# Power_Distribution_-_Spares_6-9.net
KiCad netlist of a schematic drawn in Altium Designer
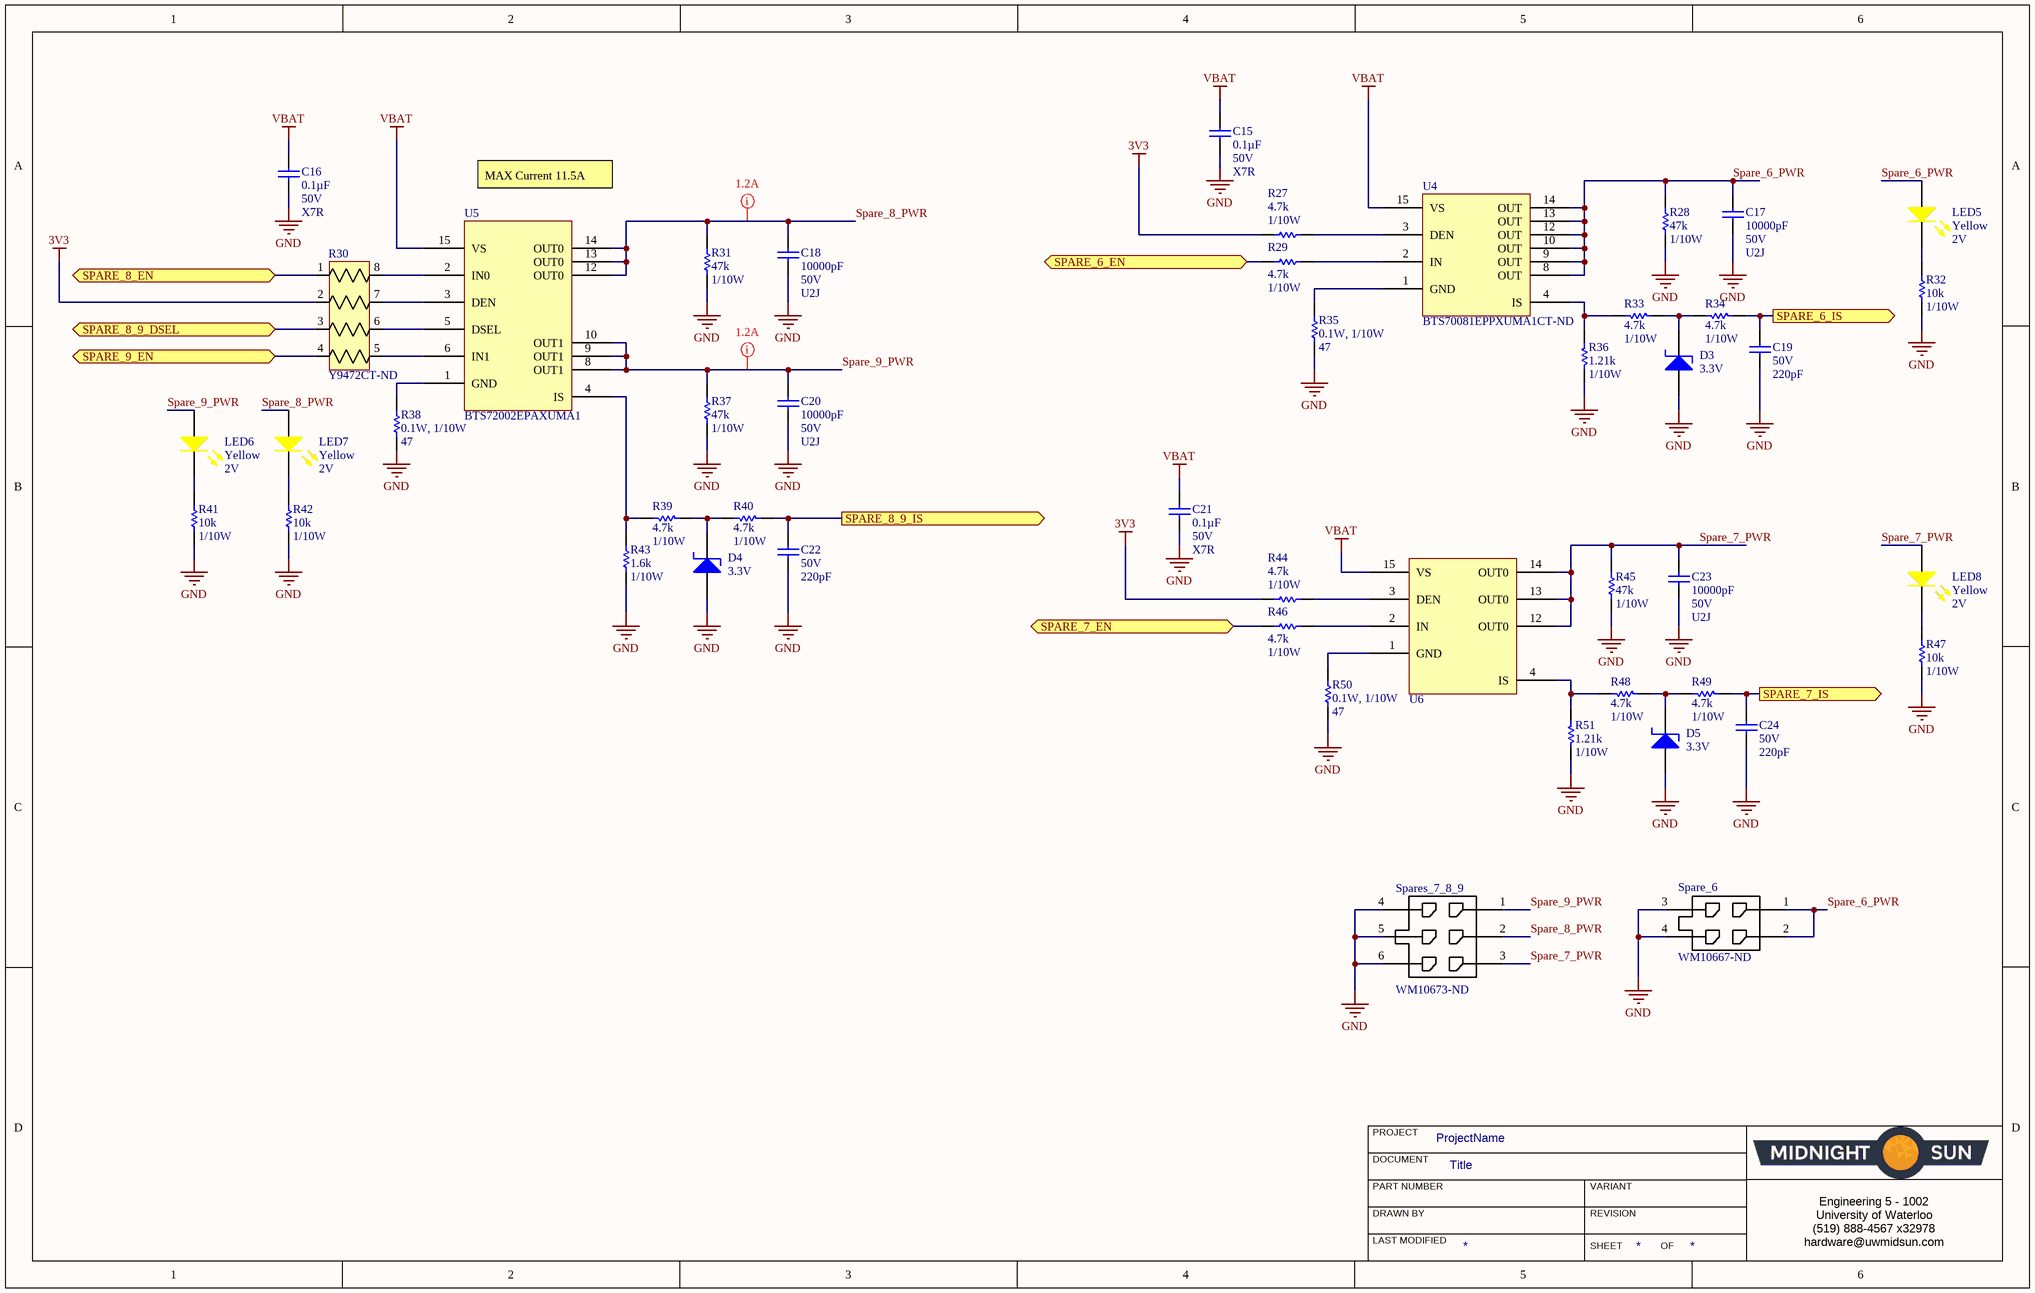
[diagram p0: Power Distribution - Spares 6-9.SchDoc]

(export (version "E")
  (design (tool "Eeschema 10.0.6"))
  (components
    (comp (ref "C15")
      (value "CAP CER 0.1UF 50V 10% X7R 0603")
      (footprint "CAP, 0603")
      (description "0.10µF ±10% 50V Ceramic Capacitor X7R 0603 (1608 Metric)")
      (fields
        (field (name "TOLERANCE") "±10%")
        (field (name "CAPACITANCE") "0.1µF")
        (field (name "VOLTAGE") "50V")
        (field (name "TEMPERATURE COEFFICIENT") "X7R")
      )
      (libsource (lib "Schematic Diagrams") (part "CAP CER 0.1UF 50V 10% X7R 0603"))
    )
    (comp (ref "C16")
      (value "CAP CER 0.1UF 50V 10% X7R 0603")
      (footprint "CAP, 0603")
      (description "0.10µF ±10% 50V Ceramic Capacitor X7R 0603 (1608 Metric)")
      (fields
        (field (name "TOLERANCE") "±10%")
        (field (name "CAPACITANCE") "0.1µF")
        (field (name "VOLTAGE") "50V")
        (field (name "TEMPERATURE COEFFICIENT") "X7R")
      )
      (libsource (lib "Schematic Diagrams") (part "CAP CER 0.1UF 50V 10% X7R 0603"))
    )
    (comp (ref "C17")
      (value "CAP CER 10nF 50V 5% X7R 0603")
      (footprint "CAP, 0603")
      (description "10000pF ±5% 50V Ceramic Capacitor U2J 0603 (1608 Metric)")
      (fields
        (field (name "TOLERANCE") "±5%")
        (field (name "CAPACITANCE") "10000pF")
        (field (name "VOLTAGE") "50V")
        (field (name "TEMPERATURE COEFFICIENT") "U2J")
      )
      (libsource (lib "Schematic Diagrams") (part "CAP CER 10nF 50V 5% X7R 0603"))
    )
    (comp (ref "C18")
      (value "CAP CER 10nF 50V 5% X7R 0603")
      (footprint "CAP, 0603")
      (description "10000pF ±5% 50V Ceramic Capacitor U2J 0603 (1608 Metric)")
      (fields
        (field (name "TOLERANCE") "±5%")
        (field (name "CAPACITANCE") "10000pF")
        (field (name "VOLTAGE") "50V")
        (field (name "TEMPERATURE COEFFICIENT") "U2J")
      )
      (libsource (lib "Schematic Diagrams") (part "CAP CER 10nF 50V 5% X7R 0603"))
    )
    (comp (ref "C19")
      (value "CAP CER 220PF 50V C0G/NP0 0603")
      (footprint "CAP, 0603")
      (description "220pF ±5% 50V Ceramic Capacitor C0G, NP0 0603 (1608 Metric)")
      (fields
        (field (name "MANUFACTURER") "KEMET")
        (field (name "TOLERANCE") "5%")
        (field (name "VOLTAGE RATING") "50V")
        (field (name "CAPACITANCE") "220pF")
      )
      (libsource (lib "Schematic Diagrams") (part "CAP CER 220PF 50V C0G/NP0 0603"))
    )
    (comp (ref "C20")
      (value "CAP CER 10nF 50V 5% X7R 0603")
      (footprint "CAP, 0603")
      (description "10000pF ±5% 50V Ceramic Capacitor U2J 0603 (1608 Metric)")
      (fields
        (field (name "TOLERANCE") "±5%")
        (field (name "CAPACITANCE") "10000pF")
        (field (name "VOLTAGE") "50V")
        (field (name "TEMPERATURE COEFFICIENT") "U2J")
      )
      (libsource (lib "Schematic Diagrams") (part "CAP CER 10nF 50V 5% X7R 0603"))
    )
    (comp (ref "C21")
      (value "CAP CER 0.1UF 50V 10% X7R 0603")
      (footprint "CAP, 0603")
      (description "0.10µF ±10% 50V Ceramic Capacitor X7R 0603 (1608 Metric)")
      (fields
        (field (name "TOLERANCE") "±10%")
        (field (name "CAPACITANCE") "0.1µF")
        (field (name "VOLTAGE") "50V")
        (field (name "TEMPERATURE COEFFICIENT") "X7R")
      )
      (libsource (lib "Schematic Diagrams") (part "CAP CER 0.1UF 50V 10% X7R 0603"))
    )
    (comp (ref "C22")
      (value "CAP CER 220PF 50V C0G/NP0 0603")
      (footprint "CAP, 0603")
      (description "220pF ±5% 50V Ceramic Capacitor C0G, NP0 0603 (1608 Metric)")
      (fields
        (field (name "MANUFACTURER") "KEMET")
        (field (name "TOLERANCE") "5%")
        (field (name "VOLTAGE RATING") "50V")
        (field (name "CAPACITANCE") "220pF")
      )
      (libsource (lib "Schematic Diagrams") (part "CAP CER 220PF 50V C0G/NP0 0603"))
    )
    (comp (ref "C23")
      (value "CAP CER 10nF 50V 5% X7R 0603")
      (footprint "CAP, 0603")
      (description "10000pF ±5% 50V Ceramic Capacitor U2J 0603 (1608 Metric)")
      (fields
        (field (name "TOLERANCE") "±5%")
        (field (name "CAPACITANCE") "10000pF")
        (field (name "VOLTAGE") "50V")
        (field (name "TEMPERATURE COEFFICIENT") "U2J")
      )
      (libsource (lib "Schematic Diagrams") (part "CAP CER 10nF 50V 5% X7R 0603"))
    )
    (comp (ref "C24")
      (value "CAP CER 220PF 50V C0G/NP0 0603")
      (footprint "CAP, 0603")
      (description "220pF ±5% 50V Ceramic Capacitor C0G, NP0 0603 (1608 Metric)")
      (fields
        (field (name "MANUFACTURER") "KEMET")
        (field (name "TOLERANCE") "5%")
        (field (name "VOLTAGE RATING") "50V")
        (field (name "CAPACITANCE") "220pF")
      )
      (libsource (lib "Schematic Diagrams") (part "CAP CER 220PF 50V C0G/NP0 0603"))
    )
    (comp (ref "D3")
      (value "DIODE ZENER 3.3V 200MW SOD323")
      (footprint "sod-323")
      (description "Zener Diode 3.3V 200mW ±5% Surface Mount SOD-323")
      (fields (field (name "VOLTAGE") "3.3V"))
      (libsource (lib "Schematic Diagrams") (part "DIODE ZENER 3.3V 200MW SOD323"))
    )
    (comp (ref "D4")
      (value "DIODE ZENER 3.3V 200MW SOD323")
      (footprint "sod-323")
      (description "Zener Diode 3.3V 200mW ±5% Surface Mount SOD-323")
      (fields (field (name "VOLTAGE") "3.3V"))
      (libsource (lib "Schematic Diagrams") (part "DIODE ZENER 3.3V 200MW SOD323"))
    )
    (comp (ref "D5")
      (value "DIODE ZENER 3.3V 200MW SOD323")
      (footprint "sod-323")
      (description "Zener Diode 3.3V 200mW ±5% Surface Mount SOD-323")
      (fields (field (name "VOLTAGE") "3.3V"))
      (libsource (lib "Schematic Diagrams") (part "DIODE ZENER 3.3V 200MW SOD323"))
    )
    (comp (ref "LED5")
      (value "LED YELLOW CLEAR 2.1V 0603")
      (footprint "LED_0603")
      (description "Yellow 590nm LED Indication - Discrete 2V 0603 (1608 Metric)")
      (fields
        (field (name "MANUFACTURER") "Wurth Electronics Inc.")
        (field (name "MANUFACTURER PART NUMBER") "150060YS75000")
        (field (name "COLOR") "Yellow")
        (field (name "VOLTAGE - FORWARD (VF) (TYP)") "2V")
      )
      (libsource (lib "Schematic Diagrams") (part "LED YELLOW CLEAR 2.1V 0603"))
    )
    (comp (ref "LED6")
      (value "LED YELLOW CLEAR 2.1V 0603")
      (footprint "LED_0603")
      (description "Yellow 590nm LED Indication - Discrete 2V 0603 (1608 Metric)")
      (fields
        (field (name "MANUFACTURER") "Wurth Electronics Inc.")
        (field (name "MANUFACTURER PART NUMBER") "150060YS75000")
        (field (name "COLOR") "Yellow")
        (field (name "VOLTAGE - FORWARD (VF) (TYP)") "2V")
      )
      (libsource (lib "Schematic Diagrams") (part "LED YELLOW CLEAR 2.1V 0603"))
    )
    (comp (ref "LED7")
      (value "LED YELLOW CLEAR 2.1V 0603")
      (footprint "LED_0603")
      (description "Yellow 590nm LED Indication - Discrete 2V 0603 (1608 Metric)")
      (fields
        (field (name "MANUFACTURER") "Wurth Electronics Inc.")
        (field (name "MANUFACTURER PART NUMBER") "150060YS75000")
        (field (name "COLOR") "Yellow")
        (field (name "VOLTAGE - FORWARD (VF) (TYP)") "2V")
      )
      (libsource (lib "Schematic Diagrams") (part "LED YELLOW CLEAR 2.1V 0603"))
    )
    (comp (ref "LED8")
      (value "LED YELLOW CLEAR 2.1V 0603")
      (footprint "LED_0603")
      (description "Yellow 590nm LED Indication - Discrete 2V 0603 (1608 Metric)")
      (fields
        (field (name "MANUFACTURER") "Wurth Electronics Inc.")
        (field (name "MANUFACTURER PART NUMBER") "150060YS75000")
        (field (name "COLOR") "Yellow")
        (field (name "VOLTAGE - FORWARD (VF) (TYP)") "2V")
      )
      (libsource (lib "Schematic Diagrams") (part "LED YELLOW CLEAR 2.1V 0603"))
    )
    (comp (ref "R27")
      (value "RES 4.7K OHM 1% 1/10W 0603")
      (footprint "RES, 0603")
      (description "4.7k Ohm ±1% 0.1W, 1/10W Chip Resistor 0603 (1608 Metric) Moisture Resistant Thick Film")
      (fields
        (field (name "TOLERANCE") "±1%")
        (field (name "RESISTANCE (OHMS)") "4.7k")
        (field (name "POWER (WATTS)") "1/10W")
      )
      (libsource (lib "Schematic Diagrams") (part "RES 4.7K OHM 1% 1/10W 0603"))
    )
    (comp (ref "R28")
      (value "RES 47K OHM 1% 1/10W 0603")
      (footprint "RES, 0603")
      (description "47 kOhms ±1% 0.1W, 1/10W Chip Resistor 0603 (1608 Metric) Automotive AEC-Q200 Thick Film")
      (fields
        (field (name "MANUFACTURER") "Panasonic")
        (field (name "MANUFACTURER PART NUMBER") "ERJ3EKF4702V")
        (field (name "RESISTANCE") "47k")
        (field (name "POWER RATING") "1/10W")
      )
      (libsource (lib "Schematic Diagrams") (part "RES 47K OHM 1% 1/10W 0603"))
    )
    (comp (ref "R29")
      (value "RES 4.7K OHM 1% 1/10W 0603")
      (footprint "RES, 0603")
      (description "4.7k Ohm ±1% 0.1W, 1/10W Chip Resistor 0603 (1608 Metric) Moisture Resistant Thick Film")
      (fields
        (field (name "TOLERANCE") "±1%")
        (field (name "RESISTANCE (OHMS)") "4.7k")
        (field (name "POWER (WATTS)") "1/10W")
      )
      (libsource (lib "Schematic Diagrams") (part "RES 4.7K OHM 1% 1/10W 0603"))
    )
    (comp (ref "R30")
      (value "RES ARRAY 4 RES 4.7K OHM 1206")
      (footprint "RES ARRAY 4RES 1206")
      (fields (field (name "TOLERANCE") "±5%") (field (name "SUPPLIER PART NUMBER 1") "Y9472CT-ND"))
      (libsource (lib "Schematic Diagrams") (part "RES ARRAY 4 RES 4.7K OHM 1206"))
    )
    (comp (ref "R31")
      (value "RES 47K OHM 1% 1/10W 0603")
      (footprint "RES, 0603")
      (description "47 kOhms ±1% 0.1W, 1/10W Chip Resistor 0603 (1608 Metric) Automotive AEC-Q200 Thick Film")
      (fields
        (field (name "MANUFACTURER") "Panasonic")
        (field (name "MANUFACTURER PART NUMBER") "ERJ3EKF4702V")
        (field (name "RESISTANCE") "47k")
        (field (name "POWER RATING") "1/10W")
      )
      (libsource (lib "Schematic Diagrams") (part "RES 47K OHM 1% 1/10W 0603"))
    )
    (comp (ref "R32")
      (value "RES 10K OHM 1% 1/10W 0603")
      (footprint "RES, 0603")
      (description "RES SMD 10K OHM 1% 1/10W 0603")
      (fields
        (field (name "TOLERANCE") "±1%")
        (field (name "RESISTANCE") "10k")
        (field (name "POWER") "1/10W")
      )
      (libsource (lib "Schematic Diagrams") (part "RES 10K OHM 1% 1/10W 0603"))
    )
    (comp (ref "R33")
      (value "RES 4.7K OHM 1% 1/10W 0603")
      (footprint "RES, 0603")
      (description "4.7k Ohm ±1% 0.1W, 1/10W Chip Resistor 0603 (1608 Metric) Moisture Resistant Thick Film")
      (fields
        (field (name "TOLERANCE") "±1%")
        (field (name "RESISTANCE (OHMS)") "4.7k")
        (field (name "POWER (WATTS)") "1/10W")
      )
      (libsource (lib "Schematic Diagrams") (part "RES 4.7K OHM 1% 1/10W 0603"))
    )
    (comp (ref "R34")
      (value "RES 4.7K OHM 1% 1/10W 0603")
      (footprint "RES, 0603")
      (description "4.7k Ohm ±1% 0.1W, 1/10W Chip Resistor 0603 (1608 Metric) Moisture Resistant Thick Film")
      (fields
        (field (name "TOLERANCE") "±1%")
        (field (name "RESISTANCE (OHMS)") "4.7k")
        (field (name "POWER (WATTS)") "1/10W")
      )
      (libsource (lib "Schematic Diagrams") (part "RES 4.7K OHM 1% 1/10W 0603"))
    )
    (comp (ref "R35")
      (value "RES SMD 47 OHM 1% 1/10W 0603")
      (footprint "RES, 0603")
      (fields
        (field (name "TOLERANCE") "±1%")
        (field (name "POWER (WATTS)") "0.1W, 1/10W")
        (field (name "VALUES") "47")
      )
      (libsource (lib "Schematic Diagrams") (part "RES SMD 47 OHM 1% 1/10W 0603"))
    )
    (comp (ref "R36")
      (value "RES 1.21K OHM 1% 1/10W 0603")
      (footprint "RES, 0603")
      (description "1.21k Ohm ±1% 0.1W, 1/10W Chip Resistor 0603 (1608 Metric) Moisture Resistant Thick Film")
      (fields
        (field (name "TOLERANCE") "±1%")
        (field (name "RESISTANCE") "1.21k")
        (field (name "POWER") "1/10W")
      )
      (libsource (lib "Schematic Diagrams") (part "RES 1.21K OHM 1% 1/10W 0603"))
    )
    (comp (ref "R37")
      (value "RES 47K OHM 1% 1/10W 0603")
      (footprint "RES, 0603")
      (description "47 kOhms ±1% 0.1W, 1/10W Chip Resistor 0603 (1608 Metric) Automotive AEC-Q200 Thick Film")
      (fields
        (field (name "MANUFACTURER") "Panasonic")
        (field (name "MANUFACTURER PART NUMBER") "ERJ3EKF4702V")
        (field (name "RESISTANCE") "47k")
        (field (name "POWER RATING") "1/10W")
      )
      (libsource (lib "Schematic Diagrams") (part "RES 47K OHM 1% 1/10W 0603"))
    )
    (comp (ref "R38")
      (value "RES SMD 47 OHM 1% 1/10W 0603")
      (footprint "RES, 0603")
      (fields
        (field (name "TOLERANCE") "±1%")
        (field (name "POWER (WATTS)") "0.1W, 1/10W")
        (field (name "VALUES") "47")
      )
      (libsource (lib "Schematic Diagrams") (part "RES SMD 47 OHM 1% 1/10W 0603"))
    )
    (comp (ref "R39")
      (value "RES 4.7K OHM 1% 1/10W 0603")
      (footprint "RES, 0603")
      (description "4.7k Ohm ±1% 0.1W, 1/10W Chip Resistor 0603 (1608 Metric) Moisture Resistant Thick Film")
      (fields
        (field (name "TOLERANCE") "±1%")
        (field (name "RESISTANCE (OHMS)") "4.7k")
        (field (name "POWER (WATTS)") "1/10W")
      )
      (libsource (lib "Schematic Diagrams") (part "RES 4.7K OHM 1% 1/10W 0603"))
    )
    (comp (ref "R40")
      (value "RES 4.7K OHM 1% 1/10W 0603")
      (footprint "RES, 0603")
      (description "4.7k Ohm ±1% 0.1W, 1/10W Chip Resistor 0603 (1608 Metric) Moisture Resistant Thick Film")
      (fields
        (field (name "TOLERANCE") "±1%")
        (field (name "RESISTANCE (OHMS)") "4.7k")
        (field (name "POWER (WATTS)") "1/10W")
      )
      (libsource (lib "Schematic Diagrams") (part "RES 4.7K OHM 1% 1/10W 0603"))
    )
    (comp (ref "R41")
      (value "RES 10K OHM 1% 1/10W 0603")
      (footprint "RES, 0603")
      (description "RES SMD 10K OHM 1% 1/10W 0603")
      (fields
        (field (name "TOLERANCE") "±1%")
        (field (name "RESISTANCE") "10k")
        (field (name "POWER") "1/10W")
      )
      (libsource (lib "Schematic Diagrams") (part "RES 10K OHM 1% 1/10W 0603"))
    )
    (comp (ref "R42")
      (value "RES 10K OHM 1% 1/10W 0603")
      (footprint "RES, 0603")
      (description "RES SMD 10K OHM 1% 1/10W 0603")
      (fields
        (field (name "TOLERANCE") "±1%")
        (field (name "RESISTANCE") "10k")
        (field (name "POWER") "1/10W")
      )
      (libsource (lib "Schematic Diagrams") (part "RES 10K OHM 1% 1/10W 0603"))
    )
    (comp (ref "R43")
      (value "RES 1.6K OHM 1% 1/10W 0603")
      (footprint "RES, 0603")
      (description "1.6 kOhms ±1% 0.1W, 1/10W Chip Resistor 0603 (1608 Metric) Moisture Resistant Thick Film")
      (fields
        (field (name "MANUFACTURER") "Yageo")
        (field (name "MANUFACTURER PART NUMBER") "RC0603FR-071K6L")
        (field (name "RESISTANCE") "1.6k")
        (field (name "POWER RATING") "1/10W")
      )
      (libsource (lib "Schematic Diagrams") (part "RES 1.6K OHM 1% 1/10W 0603"))
    )
    (comp (ref "R44")
      (value "RES 4.7K OHM 1% 1/10W 0603")
      (footprint "RES, 0603")
      (description "4.7k Ohm ±1% 0.1W, 1/10W Chip Resistor 0603 (1608 Metric) Moisture Resistant Thick Film")
      (fields
        (field (name "TOLERANCE") "±1%")
        (field (name "RESISTANCE (OHMS)") "4.7k")
        (field (name "POWER (WATTS)") "1/10W")
      )
      (libsource (lib "Schematic Diagrams") (part "RES 4.7K OHM 1% 1/10W 0603"))
    )
    (comp (ref "R45")
      (value "RES 47K OHM 1% 1/10W 0603")
      (footprint "RES, 0603")
      (description "47 kOhms ±1% 0.1W, 1/10W Chip Resistor 0603 (1608 Metric) Automotive AEC-Q200 Thick Film")
      (fields
        (field (name "MANUFACTURER") "Panasonic")
        (field (name "MANUFACTURER PART NUMBER") "ERJ3EKF4702V")
        (field (name "RESISTANCE") "47k")
        (field (name "POWER RATING") "1/10W")
      )
      (libsource (lib "Schematic Diagrams") (part "RES 47K OHM 1% 1/10W 0603"))
    )
    (comp (ref "R46")
      (value "RES 4.7K OHM 1% 1/10W 0603")
      (footprint "RES, 0603")
      (description "4.7k Ohm ±1% 0.1W, 1/10W Chip Resistor 0603 (1608 Metric) Moisture Resistant Thick Film")
      (fields
        (field (name "TOLERANCE") "±1%")
        (field (name "RESISTANCE (OHMS)") "4.7k")
        (field (name "POWER (WATTS)") "1/10W")
      )
      (libsource (lib "Schematic Diagrams") (part "RES 4.7K OHM 1% 1/10W 0603"))
    )
    (comp (ref "R47")
      (value "RES 10K OHM 1% 1/10W 0603")
      (footprint "RES, 0603")
      (description "RES SMD 10K OHM 1% 1/10W 0603")
      (fields
        (field (name "TOLERANCE") "±1%")
        (field (name "RESISTANCE") "10k")
        (field (name "POWER") "1/10W")
      )
      (libsource (lib "Schematic Diagrams") (part "RES 10K OHM 1% 1/10W 0603"))
    )
    (comp (ref "R48")
      (value "RES 4.7K OHM 1% 1/10W 0603")
      (footprint "RES, 0603")
      (description "4.7k Ohm ±1% 0.1W, 1/10W Chip Resistor 0603 (1608 Metric) Moisture Resistant Thick Film")
      (fields
        (field (name "TOLERANCE") "±1%")
        (field (name "RESISTANCE (OHMS)") "4.7k")
        (field (name "POWER (WATTS)") "1/10W")
      )
      (libsource (lib "Schematic Diagrams") (part "RES 4.7K OHM 1% 1/10W 0603"))
    )
    (comp (ref "R49")
      (value "RES 4.7K OHM 1% 1/10W 0603")
      (footprint "RES, 0603")
      (description "4.7k Ohm ±1% 0.1W, 1/10W Chip Resistor 0603 (1608 Metric) Moisture Resistant Thick Film")
      (fields
        (field (name "TOLERANCE") "±1%")
        (field (name "RESISTANCE (OHMS)") "4.7k")
        (field (name "POWER (WATTS)") "1/10W")
      )
      (libsource (lib "Schematic Diagrams") (part "RES 4.7K OHM 1% 1/10W 0603"))
    )
    (comp (ref "R50")
      (value "RES SMD 47 OHM 1% 1/10W 0603")
      (footprint "RES, 0603")
      (fields
        (field (name "TOLERANCE") "±1%")
        (field (name "POWER (WATTS)") "0.1W, 1/10W")
        (field (name "VALUES") "47")
      )
      (libsource (lib "Schematic Diagrams") (part "RES SMD 47 OHM 1% 1/10W 0603"))
    )
    (comp (ref "R51")
      (value "RES 1.21K OHM 1% 1/10W 0603")
      (footprint "RES, 0603")
      (description "1.21k Ohm ±1% 0.1W, 1/10W Chip Resistor 0603 (1608 Metric) Moisture Resistant Thick Film")
      (fields
        (field (name "TOLERANCE") "±1%")
        (field (name "RESISTANCE") "1.21k")
        (field (name "POWER") "1/10W")
      )
      (libsource (lib "Schematic Diagrams") (part "RES 1.21K OHM 1% 1/10W 0603"))
    )
    (comp (ref "Spares_7_8_9")
      (value "CONN 6POS MICRO-FIT 3mm")
      (footprint "CONN, 6POS MICRO-FIT 3MM")
      (description "Connector Header Through Hole 6 position 0.118\" (3.00mm)")
      (fields (field (name "SUPPLIER PART NUMBER 1") "WM10673-ND"))
      (libsource (lib "Schematic Diagrams") (part "CONN 6POS MICRO-FIT 3mm"))
    )
    (comp (ref "Spare_6")
      (value "CONN 4POS MICRO-FIT 3mm")
      (footprint "CONN 4POS MICROFIT (2x2)")
      (fields
        (field (name "MANUFACTURER") "Molex, LLC")
        (field (name "MANUFACTURER PART NUMBER") "430450427")
        (field (name "SUPPLIER PART NUMBER 1") "WM10667-ND")
      )
      (libsource (lib "Schematic Diagrams") (part "CONN 4POS MICRO-FIT 3mm"))
    )
    (comp (ref "U4")
      (value "IC LOAD SWITCH BTS70081EPPXUMA1")
      (footprint "IC LOAD SWITCH PG-TSDSO-14-22")
      (description "Power Switch/Driver 1:1 N-Channel 11A PG-TSDSO-14-22")
      (fields
        (field (name "MANUFACTURER") "Infineon")
        (field (name "MANUFACTURER PART NUMBER") "BTS70081EPPXUMA1CT-ND")
      )
      (libsource (lib "Schematic Diagrams") (part "IC LOAD SWITCH BTS70081EPPXUMA1"))
    )
    (comp (ref "U5")
      (value "IC LOAD SWITCH BTS7200-2EPA PG-TSDSO-14_1")
      (footprint "IC LOAD SWITCH PG-TSDSO-14-22")
      (description "Power Switch/Driver 1:1 N-Channel 1.2A PG-TSDSO-14-22")
      (fields
        (field (name "MANUFACTURER") "Infineon")
        (field (name "MANUFACTURER PART NUMBER") "BTS72002EPAXUMA1")
      )
      (libsource (lib "Schematic Diagrams") (part "IC LOAD SWITCH BTS7200-2EPA PG-TSDSO-14_1"))
    )
    (comp (ref "U6")
      (value "IC LOAD SWITCH BTS70401EPA PG-TSDSO-14-22")
      (footprint "IC LOAD SWITCH PG-TSDSO-14-22")
      (description "Power Switch/Driver 1:1 N-Channel 4.5A PG-TSDSO-14-22")
      (fields
        (field (name "MANUFACTURER") "Infineon")
        (field (name "MANUFACTURER PART NUMBER") "BTS70401EPAXUMA1")
      )
      (libsource (lib "Schematic Diagrams") (part "IC LOAD SWITCH BTS70401EPA PG-TSDSO-14-22"))
    )
  )
  (nets
    (net (code "1") (name "/SPARE_6_EN") (class "Default")
      (node (ref "R29") (pin "1") (pinfunction "1_1") (pintype "passive"))
    )
    (net (code "2") (name "/SPARE_6_IS") (class "Default")
      (node (ref "C19") (pin "1") (pinfunction "1_1") (pintype "passive"))
      (node (ref "R34") (pin "1") (pinfunction "1_1") (pintype "passive"))
    )
    (net (code "3") (name "/SPARE_7_EN") (class "Default")
      (node (ref "R46") (pin "1") (pinfunction "1_1") (pintype "passive"))
    )
    (net (code "4") (name "/SPARE_7_IS") (class "Default")
      (node (ref "C24") (pin "1") (pinfunction "1_1") (pintype "passive"))
      (node (ref "R49") (pin "1") (pinfunction "1_1") (pintype "passive"))
    )
    (net (code "5") (name "/SPARE_8_9_DSEL") (class "Default")
      (node (ref "R30") (pin "3") (pinfunction "3_3") (pintype "passive"))
    )
    (net (code "6") (name "/SPARE_8_9_IS") (class "Default")
      (node (ref "C22") (pin "1") (pinfunction "1_1") (pintype "passive"))
      (node (ref "R40") (pin "1") (pinfunction "1_1") (pintype "passive"))
    )
    (net (code "7") (name "/SPARE_8_EN") (class "Default")
      (node (ref "R30") (pin "1") (pinfunction "1_1") (pintype "passive"))
    )
    (net (code "8") (name "/SPARE_9_EN") (class "Default")
      (node (ref "R30") (pin "4") (pinfunction "4_4") (pintype "passive"))
    )
    (net (code "9") (name "/Spare_6_PWR") (class "Default")
      (node (ref "C17") (pin "1") (pinfunction "1_1") (pintype "passive"))
      (node (ref "LED5") (pin "1") (pinfunction "A_1") (pintype "passive"))
      (node (ref "R28") (pin "1") (pinfunction "1_1") (pintype "passive"))
      (node (ref "Spare_6") (pin "1") (pinfunction "1_1") (pintype "passive"))
      (node (ref "Spare_6") (pin "2") (pinfunction "2_2") (pintype "passive"))
      (node (ref "U4") (pin "10") (pinfunction "OUT_10") (pintype "passive"))
      (node (ref "U4") (pin "12") (pinfunction "OUT_12") (pintype "passive"))
      (node (ref "U4") (pin "13") (pinfunction "OUT_13") (pintype "passive"))
      (node (ref "U4") (pin "14") (pinfunction "OUT_14") (pintype "passive"))
      (node (ref "U4") (pin "8") (pinfunction "OUT_8") (pintype "passive"))
      (node (ref "U4") (pin "9") (pinfunction "OUT_9") (pintype "passive"))
    )
    (net (code "10") (name "/Spare_7_PWR") (class "Default")
      (node (ref "C23") (pin "1") (pinfunction "1_1") (pintype "passive"))
      (node (ref "LED8") (pin "1") (pinfunction "A_1") (pintype "passive"))
      (node (ref "R45") (pin "1") (pinfunction "1_1") (pintype "passive"))
      (node (ref "Spares_7_8_9") (pin "3") (pinfunction "3_3") (pintype "passive"))
      (node (ref "U6") (pin "12") (pinfunction "OUT0_12") (pintype "passive"))
      (node (ref "U6") (pin "13") (pinfunction "OUT0_13") (pintype "passive"))
      (node (ref "U6") (pin "14") (pinfunction "OUT0_14") (pintype "passive"))
    )
    (net (code "11") (name "/Spare_8_PWR") (class "Default")
      (node (ref "C18") (pin "1") (pinfunction "1_1") (pintype "passive"))
      (node (ref "LED7") (pin "1") (pinfunction "A_1") (pintype "passive"))
      (node (ref "R31") (pin "1") (pinfunction "1_1") (pintype "passive"))
      (node (ref "Spares_7_8_9") (pin "2") (pinfunction "2_2") (pintype "passive"))
      (node (ref "U5") (pin "12") (pinfunction "OUT0_12") (pintype "passive"))
      (node (ref "U5") (pin "13") (pinfunction "OUT0_13") (pintype "passive"))
      (node (ref "U5") (pin "14") (pinfunction "OUT0_14") (pintype "passive"))
    )
    (net (code "12") (name "/Spare_9_PWR") (class "Default")
      (node (ref "C20") (pin "1") (pinfunction "1_1") (pintype "passive"))
      (node (ref "LED6") (pin "1") (pinfunction "A_1") (pintype "passive"))
      (node (ref "R37") (pin "1") (pinfunction "1_1") (pintype "passive"))
      (node (ref "Spares_7_8_9") (pin "1") (pinfunction "1_1") (pintype "passive"))
      (node (ref "U5") (pin "10") (pinfunction "OUT1_10") (pintype "passive"))
      (node (ref "U5") (pin "8") (pinfunction "OUT1_8") (pintype "passive"))
      (node (ref "U5") (pin "9") (pinfunction "OUT1_9") (pintype "passive"))
    )
    (net (code "13") (name "3V3") (class "Default")
      (node (ref "R27") (pin "1") (pinfunction "1_1") (pintype "passive"))
      (node (ref "R30") (pin "2") (pinfunction "2_2") (pintype "passive"))
      (node (ref "R44") (pin "1") (pinfunction "1_1") (pintype "passive"))
    )
    (net (code "14") (name "GND") (class "Default")
      (node (ref "C15") (pin "2") (pinfunction "2_2") (pintype "passive"))
      (node (ref "C16") (pin "2") (pinfunction "2_2") (pintype "passive"))
      (node (ref "C17") (pin "2") (pinfunction "2_2") (pintype "passive"))
      (node (ref "C18") (pin "2") (pinfunction "2_2") (pintype "passive"))
      (node (ref "C19") (pin "2") (pinfunction "2_2") (pintype "passive"))
      (node (ref "C20") (pin "2") (pinfunction "2_2") (pintype "passive"))
      (node (ref "C21") (pin "2") (pinfunction "2_2") (pintype "passive"))
      (node (ref "C22") (pin "2") (pinfunction "2_2") (pintype "passive"))
      (node (ref "C23") (pin "2") (pinfunction "2_2") (pintype "passive"))
      (node (ref "C24") (pin "2") (pinfunction "2_2") (pintype "passive"))
      (node (ref "D3") (pin "1") (pinfunction "A_1") (pintype "passive"))
      (node (ref "D4") (pin "1") (pinfunction "A_1") (pintype "passive"))
      (node (ref "D5") (pin "1") (pinfunction "A_1") (pintype "passive"))
      (node (ref "R28") (pin "2") (pinfunction "2_2") (pintype "passive"))
      (node (ref "R31") (pin "2") (pinfunction "2_2") (pintype "passive"))
      (node (ref "R32") (pin "2") (pinfunction "2_2") (pintype "passive"))
      (node (ref "R35") (pin "2") (pinfunction "2_2") (pintype "passive"))
      (node (ref "R36") (pin "2") (pinfunction "2_2") (pintype "passive"))
      (node (ref "R37") (pin "2") (pinfunction "2_2") (pintype "passive"))
      (node (ref "R38") (pin "2") (pinfunction "2_2") (pintype "passive"))
      (node (ref "R41") (pin "2") (pinfunction "2_2") (pintype "passive"))
      (node (ref "R42") (pin "2") (pinfunction "2_2") (pintype "passive"))
      (node (ref "R43") (pin "2") (pinfunction "2_2") (pintype "passive"))
      (node (ref "R45") (pin "2") (pinfunction "2_2") (pintype "passive"))
      (node (ref "R47") (pin "2") (pinfunction "2_2") (pintype "passive"))
      (node (ref "R50") (pin "2") (pinfunction "2_2") (pintype "passive"))
      (node (ref "R51") (pin "2") (pinfunction "2_2") (pintype "passive"))
      (node (ref "Spare_6") (pin "3") (pinfunction "3_3") (pintype "passive"))
      (node (ref "Spare_6") (pin "4") (pinfunction "4_4") (pintype "passive"))
      (node (ref "Spares_7_8_9") (pin "4") (pinfunction "4_4") (pintype "passive"))
      (node (ref "Spares_7_8_9") (pin "5") (pinfunction "5_5") (pintype "passive"))
      (node (ref "Spares_7_8_9") (pin "6") (pinfunction "6_6") (pintype "passive"))
    )
    (net (code "15") (name "Net-(D3-K)") (class "Default")
      (node (ref "D3") (pin "2") (pinfunction "K_2") (pintype "passive"))
      (node (ref "R33") (pin "1") (pinfunction "1_1") (pintype "passive"))
      (node (ref "R34") (pin "2") (pinfunction "2_2") (pintype "passive"))
    )
    (net (code "16") (name "Net-(D4-K)") (class "Default")
      (node (ref "D4") (pin "2") (pinfunction "K_2") (pintype "passive"))
      (node (ref "R39") (pin "1") (pinfunction "1_1") (pintype "passive"))
      (node (ref "R40") (pin "2") (pinfunction "2_2") (pintype "passive"))
    )
    (net (code "17") (name "Net-(D5-K)") (class "Default")
      (node (ref "D5") (pin "2") (pinfunction "K_2") (pintype "passive"))
      (node (ref "R48") (pin "1") (pinfunction "1_1") (pintype "passive"))
      (node (ref "R49") (pin "2") (pinfunction "2_2") (pintype "passive"))
    )
    (net (code "18") (name "Net-(LED5-K)") (class "Default")
      (node (ref "LED5") (pin "2") (pinfunction "K_2") (pintype "passive"))
      (node (ref "R32") (pin "1") (pinfunction "1_1") (pintype "passive"))
    )
    (net (code "19") (name "Net-(LED6-K)") (class "Default")
      (node (ref "LED6") (pin "2") (pinfunction "K_2") (pintype "passive"))
      (node (ref "R41") (pin "1") (pinfunction "1_1") (pintype "passive"))
    )
    (net (code "20") (name "Net-(LED7-K)") (class "Default")
      (node (ref "LED7") (pin "2") (pinfunction "K_2") (pintype "passive"))
      (node (ref "R42") (pin "1") (pinfunction "1_1") (pintype "passive"))
    )
    (net (code "21") (name "Net-(LED8-K)") (class "Default")
      (node (ref "LED8") (pin "2") (pinfunction "K_2") (pintype "passive"))
      (node (ref "R47") (pin "1") (pinfunction "1_1") (pintype "passive"))
    )
    (net (code "22") (name "Net-(U4-DEN)") (class "Default")
      (node (ref "R27") (pin "2") (pinfunction "2_2") (pintype "passive"))
      (node (ref "U4") (pin "3") (pinfunction "DEN_3") (pintype "passive"))
    )
    (net (code "23") (name "Net-(U4-GND)") (class "Default")
      (node (ref "R35") (pin "1") (pinfunction "1_1") (pintype "passive"))
      (node (ref "U4") (pin "1") (pinfunction "GND_1") (pintype "passive"))
    )
    (net (code "24") (name "Net-(U4-IN)") (class "Default")
      (node (ref "R29") (pin "2") (pinfunction "2_2") (pintype "passive"))
      (node (ref "U4") (pin "2") (pinfunction "IN_2") (pintype "passive"))
    )
    (net (code "25") (name "Net-(U4-IS)") (class "Default")
      (node (ref "R33") (pin "2") (pinfunction "2_2") (pintype "passive"))
      (node (ref "R36") (pin "1") (pinfunction "1_1") (pintype "passive"))
      (node (ref "U4") (pin "4") (pinfunction "IS_4") (pintype "passive"))
    )
    (net (code "26") (name "Net-(U5-DEN)") (class "Default")
      (node (ref "R30") (pin "7") (pinfunction "7_7") (pintype "passive"))
      (node (ref "U5") (pin "3") (pinfunction "DEN_3") (pintype "passive"))
    )
    (net (code "27") (name "Net-(U5-DSEL)") (class "Default")
      (node (ref "R30") (pin "6") (pinfunction "6_6") (pintype "passive"))
      (node (ref "U5") (pin "5") (pinfunction "DSEL_5") (pintype "passive"))
    )
    (net (code "28") (name "Net-(U5-GND)") (class "Default")
      (node (ref "R38") (pin "1") (pinfunction "1_1") (pintype "passive"))
      (node (ref "U5") (pin "1") (pinfunction "GND_1") (pintype "passive"))
    )
    (net (code "29") (name "Net-(U5-IN0)") (class "Default")
      (node (ref "R30") (pin "8") (pinfunction "8_8") (pintype "passive"))
      (node (ref "U5") (pin "2") (pinfunction "IN0_2") (pintype "passive"))
    )
    (net (code "30") (name "Net-(U5-IN1)") (class "Default")
      (node (ref "R30") (pin "5") (pinfunction "5_5") (pintype "passive"))
      (node (ref "U5") (pin "6") (pinfunction "IN1_6") (pintype "passive"))
    )
    (net (code "31") (name "Net-(U5-IS)") (class "Default")
      (node (ref "R39") (pin "2") (pinfunction "2_2") (pintype "passive"))
      (node (ref "R43") (pin "1") (pinfunction "1_1") (pintype "passive"))
      (node (ref "U5") (pin "4") (pinfunction "IS_4") (pintype "passive"))
    )
    (net (code "32") (name "Net-(U6-DEN)") (class "Default")
      (node (ref "R44") (pin "2") (pinfunction "2_2") (pintype "passive"))
      (node (ref "U6") (pin "3") (pinfunction "DEN_3") (pintype "passive"))
    )
    (net (code "33") (name "Net-(U6-GND)") (class "Default")
      (node (ref "R50") (pin "1") (pinfunction "1_1") (pintype "passive"))
      (node (ref "U6") (pin "1") (pinfunction "GND_1") (pintype "passive"))
    )
    (net (code "34") (name "Net-(U6-IN)") (class "Default")
      (node (ref "R46") (pin "2") (pinfunction "2_2") (pintype "passive"))
      (node (ref "U6") (pin "2") (pinfunction "IN_2") (pintype "passive"))
    )
    (net (code "35") (name "Net-(U6-IS)") (class "Default")
      (node (ref "R48") (pin "2") (pinfunction "2_2") (pintype "passive"))
      (node (ref "R51") (pin "1") (pinfunction "1_1") (pintype "passive"))
      (node (ref "U6") (pin "4") (pinfunction "IS_4") (pintype "passive"))
    )
    (net (code "36") (name "VBAT") (class "Default")
      (node (ref "C15") (pin "1") (pinfunction "1_1") (pintype "passive"))
      (node (ref "C16") (pin "1") (pinfunction "1_1") (pintype "passive"))
      (node (ref "C21") (pin "1") (pinfunction "1_1") (pintype "passive"))
      (node (ref "U4") (pin "15") (pinfunction "VS_15") (pintype "passive"))
      (node (ref "U5") (pin "15") (pinfunction "VS_15") (pintype "passive"))
      (node (ref "U6") (pin "15") (pinfunction "VS_15") (pintype "passive"))
    )
  )
)
